# 40_Pin_Relocator.net
KiCad netlist of a schematic drawn in EAGLE
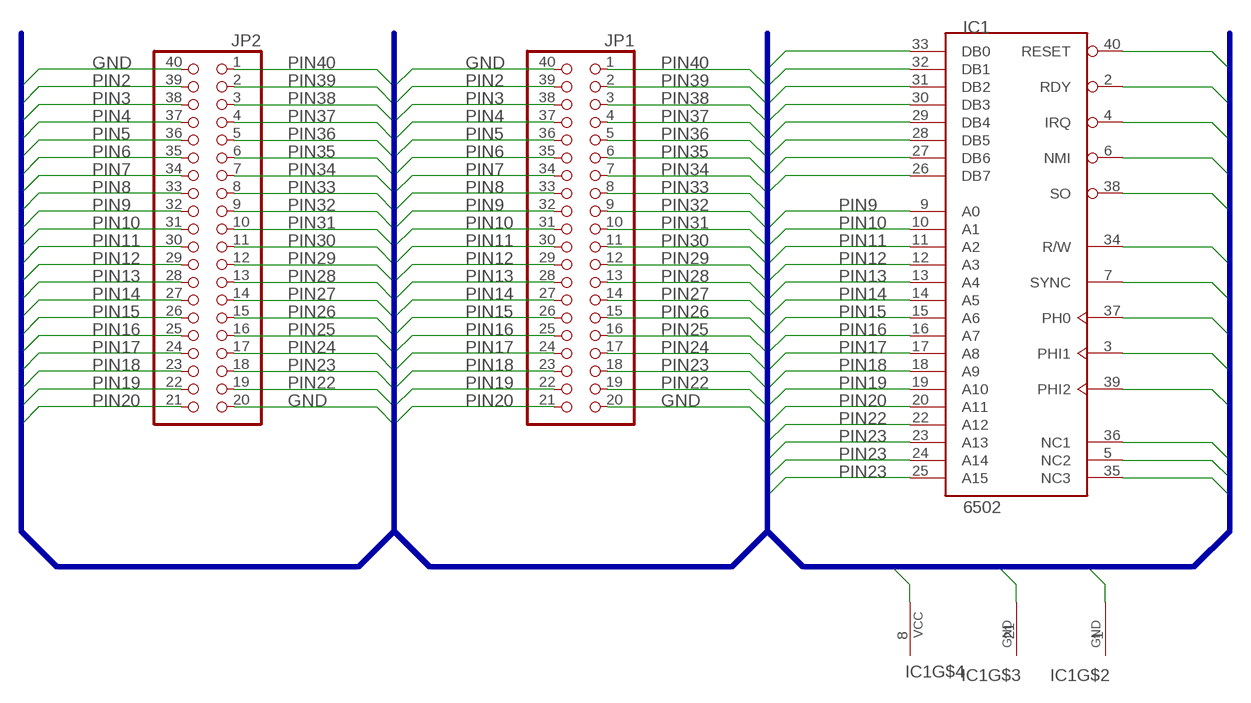
[diagram p0: schematic, sheet 1]

(export (version "E")
  (design (tool "Eeschema 10.0.6"))
  (components
    (comp (ref "IC1")
      (value "6502")
      (footprint "eagle-import:DIP40")
      (libsource (lib "eagle-import") (part "6502"))
    )
    (comp (ref "JP1")
      (value "PINHD-2X20")
      (footprint "eagle-import:2X20")
      (libsource (lib "eagle-import") (part "PINHD-2X20"))
    )
    (comp (ref "JP2")
      (value "PINHD-2X20")
      (footprint "eagle-import:2X20")
      (libsource (lib "eagle-import") (part "PINHD-2X20"))
    )
  )
  (nets
    (net (code "3") (name "/GND") (class "Default")
      (node (ref "IC1") (pin "1") (pinfunction "GND_1") (pintype "power_in"))
      (node (ref "IC1") (pin "21") (pinfunction "GND_21") (pintype "power_in"))
      (node (ref "JP1") (pin "20") (pinfunction "39_20") (pintype "passive"))
      (node (ref "JP1") (pin "40") (pinfunction "2_40") (pintype "passive"))
      (node (ref "JP2") (pin "20") (pinfunction "39_20") (pintype "passive"))
      (node (ref "JP2") (pin "40") (pinfunction "2_40") (pintype "passive"))
    )
    (net (code "4") (name "/PIN2") (class "Default")
      (node (ref "IC1") (pin "2") (pinfunction "RDY_2") (pintype "input"))
      (node (ref "JP1") (pin "39") (pinfunction "4_39") (pintype "passive"))
      (node (ref "JP2") (pin "39") (pinfunction "4_39") (pintype "passive"))
    )
    (net (code "5") (name "/PIN3") (class "Default")
      (node (ref "IC1") (pin "3") (pinfunction "PHI1_3") (pintype "output"))
      (node (ref "JP1") (pin "38") (pinfunction "6_38") (pintype "passive"))
      (node (ref "JP2") (pin "38") (pinfunction "6_38") (pintype "passive"))
    )
    (net (code "6") (name "/PIN4") (class "Default")
      (node (ref "IC1") (pin "4") (pinfunction "IRQ_4") (pintype "input"))
      (node (ref "JP1") (pin "37") (pinfunction "8_37") (pintype "passive"))
      (node (ref "JP2") (pin "37") (pinfunction "8_37") (pintype "passive"))
    )
    (net (code "7") (name "/PIN5") (class "Default")
      (node (ref "IC1") (pin "5") (pinfunction "NC2_5") (pintype "passive"))
      (node (ref "JP1") (pin "36") (pinfunction "10_36") (pintype "passive"))
      (node (ref "JP2") (pin "36") (pinfunction "10_36") (pintype "passive"))
    )
    (net (code "8") (name "/PIN6") (class "Default")
      (node (ref "IC1") (pin "6") (pinfunction "NMI_6") (pintype "input"))
      (node (ref "JP1") (pin "35") (pinfunction "12_35") (pintype "passive"))
      (node (ref "JP2") (pin "35") (pinfunction "12_35") (pintype "passive"))
    )
    (net (code "9") (name "/PIN7") (class "Default")
      (node (ref "IC1") (pin "7") (pinfunction "SYNC_7") (pintype "output"))
      (node (ref "JP1") (pin "34") (pinfunction "14_34") (pintype "passive"))
      (node (ref "JP2") (pin "34") (pinfunction "14_34") (pintype "passive"))
    )
    (net (code "10") (name "/PIN8") (class "Default")
      (node (ref "IC1") (pin "8") (pinfunction "VCC_8") (pintype "power_in"))
      (node (ref "JP1") (pin "33") (pinfunction "16_33") (pintype "passive"))
      (node (ref "JP2") (pin "33") (pinfunction "16_33") (pintype "passive"))
    )
    (net (code "11") (name "/PIN9") (class "Default")
      (node (ref "IC1") (pin "9") (pinfunction "A0_9") (pintype "output"))
      (node (ref "JP1") (pin "32") (pinfunction "18_32") (pintype "passive"))
      (node (ref "JP2") (pin "32") (pinfunction "18_32") (pintype "passive"))
    )
    (net (code "12") (name "/PIN10") (class "Default")
      (node (ref "IC1") (pin "10") (pinfunction "A1_10") (pintype "output"))
      (node (ref "JP1") (pin "31") (pinfunction "20_31") (pintype "passive"))
      (node (ref "JP2") (pin "31") (pinfunction "20_31") (pintype "passive"))
    )
    (net (code "13") (name "/PIN11") (class "Default")
      (node (ref "IC1") (pin "11") (pinfunction "A2_11") (pintype "output"))
      (node (ref "JP1") (pin "30") (pinfunction "22_30") (pintype "passive"))
      (node (ref "JP2") (pin "30") (pinfunction "22_30") (pintype "passive"))
    )
    (net (code "14") (name "/PIN12") (class "Default")
      (node (ref "IC1") (pin "12") (pinfunction "A3_12") (pintype "output"))
      (node (ref "JP1") (pin "29") (pinfunction "24_29") (pintype "passive"))
      (node (ref "JP2") (pin "29") (pinfunction "24_29") (pintype "passive"))
    )
    (net (code "15") (name "/PIN13") (class "Default")
      (node (ref "IC1") (pin "13") (pinfunction "A4_13") (pintype "output"))
      (node (ref "JP1") (pin "28") (pinfunction "26_28") (pintype "passive"))
      (node (ref "JP2") (pin "28") (pinfunction "26_28") (pintype "passive"))
    )
    (net (code "16") (name "/PIN14") (class "Default")
      (node (ref "IC1") (pin "14") (pinfunction "A5_14") (pintype "output"))
      (node (ref "JP1") (pin "27") (pinfunction "28_27") (pintype "passive"))
      (node (ref "JP2") (pin "27") (pinfunction "28_27") (pintype "passive"))
    )
    (net (code "17") (name "/PIN15") (class "Default")
      (node (ref "IC1") (pin "15") (pinfunction "A6_15") (pintype "output"))
      (node (ref "JP1") (pin "26") (pinfunction "30_26") (pintype "passive"))
      (node (ref "JP2") (pin "26") (pinfunction "30_26") (pintype "passive"))
    )
    (net (code "18") (name "/PIN16") (class "Default")
      (node (ref "IC1") (pin "16") (pinfunction "A7_16") (pintype "output"))
      (node (ref "JP1") (pin "25") (pinfunction "32_25") (pintype "passive"))
      (node (ref "JP2") (pin "25") (pinfunction "32_25") (pintype "passive"))
    )
    (net (code "19") (name "/PIN17") (class "Default")
      (node (ref "IC1") (pin "17") (pinfunction "A8_17") (pintype "output"))
      (node (ref "JP1") (pin "24") (pinfunction "34_24") (pintype "passive"))
      (node (ref "JP2") (pin "24") (pinfunction "34_24") (pintype "passive"))
    )
    (net (code "20") (name "/PIN18") (class "Default")
      (node (ref "IC1") (pin "18") (pinfunction "A9_18") (pintype "output"))
      (node (ref "JP1") (pin "23") (pinfunction "36_23") (pintype "passive"))
      (node (ref "JP2") (pin "23") (pinfunction "36_23") (pintype "passive"))
    )
    (net (code "21") (name "/PIN19") (class "Default")
      (node (ref "IC1") (pin "19") (pinfunction "A10_19") (pintype "output"))
      (node (ref "JP1") (pin "22") (pinfunction "38_22") (pintype "passive"))
      (node (ref "JP2") (pin "22") (pinfunction "38_22") (pintype "passive"))
    )
    (net (code "22") (name "/PIN20") (class "Default")
      (node (ref "IC1") (pin "20") (pinfunction "A11_20") (pintype "output"))
      (node (ref "JP1") (pin "21") (pinfunction "40_21") (pintype "passive"))
      (node (ref "JP2") (pin "21") (pinfunction "40_21") (pintype "passive"))
    )
    (net (code "23") (name "/PIN22") (class "Default")
      (node (ref "IC1") (pin "22") (pinfunction "A12_22") (pintype "output"))
      (node (ref "JP1") (pin "19") (pinfunction "37_19") (pintype "passive"))
      (node (ref "JP2") (pin "19") (pinfunction "37_19") (pintype "passive"))
    )
    (net (code "24") (name "/PIN23") (class "Default")
      (node (ref "IC1") (pin "23") (pinfunction "A13_23") (pintype "output"))
      (node (ref "JP1") (pin "18") (pinfunction "35_18") (pintype "passive"))
      (node (ref "JP2") (pin "18") (pinfunction "35_18") (pintype "passive"))
    )
    (net (code "25") (name "/PIN24") (class "Default")
      (node (ref "IC1") (pin "24") (pinfunction "A14_24") (pintype "output"))
      (node (ref "JP1") (pin "17") (pinfunction "33_17") (pintype "passive"))
      (node (ref "JP2") (pin "17") (pinfunction "33_17") (pintype "passive"))
    )
    (net (code "26") (name "/PIN25") (class "Default")
      (node (ref "IC1") (pin "25") (pinfunction "A15_25") (pintype "output"))
      (node (ref "JP1") (pin "16") (pinfunction "31_16") (pintype "passive"))
      (node (ref "JP2") (pin "16") (pinfunction "31_16") (pintype "passive"))
    )
    (net (code "27") (name "/PIN26") (class "Default")
      (node (ref "IC1") (pin "26") (pinfunction "DB7_26") (pintype "bidirectional"))
      (node (ref "JP1") (pin "15") (pinfunction "29_15") (pintype "passive"))
      (node (ref "JP2") (pin "15") (pinfunction "29_15") (pintype "passive"))
    )
    (net (code "28") (name "/PIN27") (class "Default")
      (node (ref "IC1") (pin "27") (pinfunction "DB6_27") (pintype "bidirectional"))
      (node (ref "JP1") (pin "14") (pinfunction "27_14") (pintype "passive"))
      (node (ref "JP2") (pin "14") (pinfunction "27_14") (pintype "passive"))
    )
    (net (code "29") (name "/PIN28") (class "Default")
      (node (ref "IC1") (pin "28") (pinfunction "DB5_28") (pintype "bidirectional"))
      (node (ref "JP1") (pin "13") (pinfunction "25_13") (pintype "passive"))
      (node (ref "JP2") (pin "13") (pinfunction "25_13") (pintype "passive"))
    )
    (net (code "30") (name "/PIN29") (class "Default")
      (node (ref "IC1") (pin "29") (pinfunction "DB4_29") (pintype "bidirectional"))
      (node (ref "JP1") (pin "12") (pinfunction "23_12") (pintype "passive"))
      (node (ref "JP2") (pin "12") (pinfunction "23_12") (pintype "passive"))
    )
    (net (code "31") (name "/PIN30") (class "Default")
      (node (ref "IC1") (pin "30") (pinfunction "DB3_30") (pintype "bidirectional"))
      (node (ref "JP1") (pin "11") (pinfunction "21_11") (pintype "passive"))
      (node (ref "JP2") (pin "11") (pinfunction "21_11") (pintype "passive"))
    )
    (net (code "32") (name "/PIN31") (class "Default")
      (node (ref "IC1") (pin "31") (pinfunction "DB2_31") (pintype "bidirectional"))
      (node (ref "JP1") (pin "10") (pinfunction "19_10") (pintype "passive"))
      (node (ref "JP2") (pin "10") (pinfunction "19_10") (pintype "passive"))
    )
    (net (code "33") (name "/PIN32") (class "Default")
      (node (ref "IC1") (pin "32") (pinfunction "DB1_32") (pintype "bidirectional"))
      (node (ref "JP1") (pin "9") (pinfunction "17_9") (pintype "passive"))
      (node (ref "JP2") (pin "9") (pinfunction "17_9") (pintype "passive"))
    )
    (net (code "34") (name "/PIN33") (class "Default")
      (node (ref "IC1") (pin "33") (pinfunction "DB0_33") (pintype "bidirectional"))
      (node (ref "JP1") (pin "8") (pinfunction "15_8") (pintype "passive"))
      (node (ref "JP2") (pin "8") (pinfunction "15_8") (pintype "passive"))
    )
    (net (code "35") (name "/PIN34") (class "Default")
      (node (ref "IC1") (pin "34") (pinfunction "R/W_34") (pintype "output"))
      (node (ref "JP1") (pin "7") (pinfunction "13_7") (pintype "passive"))
      (node (ref "JP2") (pin "7") (pinfunction "13_7") (pintype "passive"))
    )
    (net (code "36") (name "/PIN35") (class "Default")
      (node (ref "IC1") (pin "35") (pinfunction "NC3_35") (pintype "passive"))
      (node (ref "JP1") (pin "6") (pinfunction "11_6") (pintype "passive"))
      (node (ref "JP2") (pin "6") (pinfunction "11_6") (pintype "passive"))
    )
    (net (code "37") (name "/PIN36") (class "Default")
      (node (ref "IC1") (pin "36") (pinfunction "NC1_36") (pintype "passive"))
      (node (ref "JP1") (pin "5") (pinfunction "9_5") (pintype "passive"))
      (node (ref "JP2") (pin "5") (pinfunction "9_5") (pintype "passive"))
    )
    (net (code "38") (name "/PIN37") (class "Default")
      (node (ref "IC1") (pin "37") (pinfunction "PH0_37") (pintype "input"))
      (node (ref "JP1") (pin "4") (pinfunction "7_4") (pintype "passive"))
      (node (ref "JP2") (pin "4") (pinfunction "7_4") (pintype "passive"))
    )
    (net (code "39") (name "/PIN38") (class "Default")
      (node (ref "IC1") (pin "38") (pinfunction "SO_38") (pintype "input"))
      (node (ref "JP1") (pin "3") (pinfunction "5_3") (pintype "passive"))
      (node (ref "JP2") (pin "3") (pinfunction "5_3") (pintype "passive"))
    )
    (net (code "40") (name "/PIN39") (class "Default")
      (node (ref "IC1") (pin "39") (pinfunction "PHI2_39") (pintype "output"))
      (node (ref "JP1") (pin "2") (pinfunction "3_2") (pintype "passive"))
      (node (ref "JP2") (pin "2") (pinfunction "3_2") (pintype "passive"))
    )
    (net (code "41") (name "/PIN40") (class "Default")
      (node (ref "IC1") (pin "40") (pinfunction "RESET_40") (pintype "input"))
      (node (ref "JP1") (pin "1") (pinfunction "1_1") (pintype "passive"))
      (node (ref "JP2") (pin "1") (pinfunction "1_1") (pintype "passive"))
    )
  )
)
